# Board1_V4.net
KiCad netlist of a schematic drawn in EAGLE
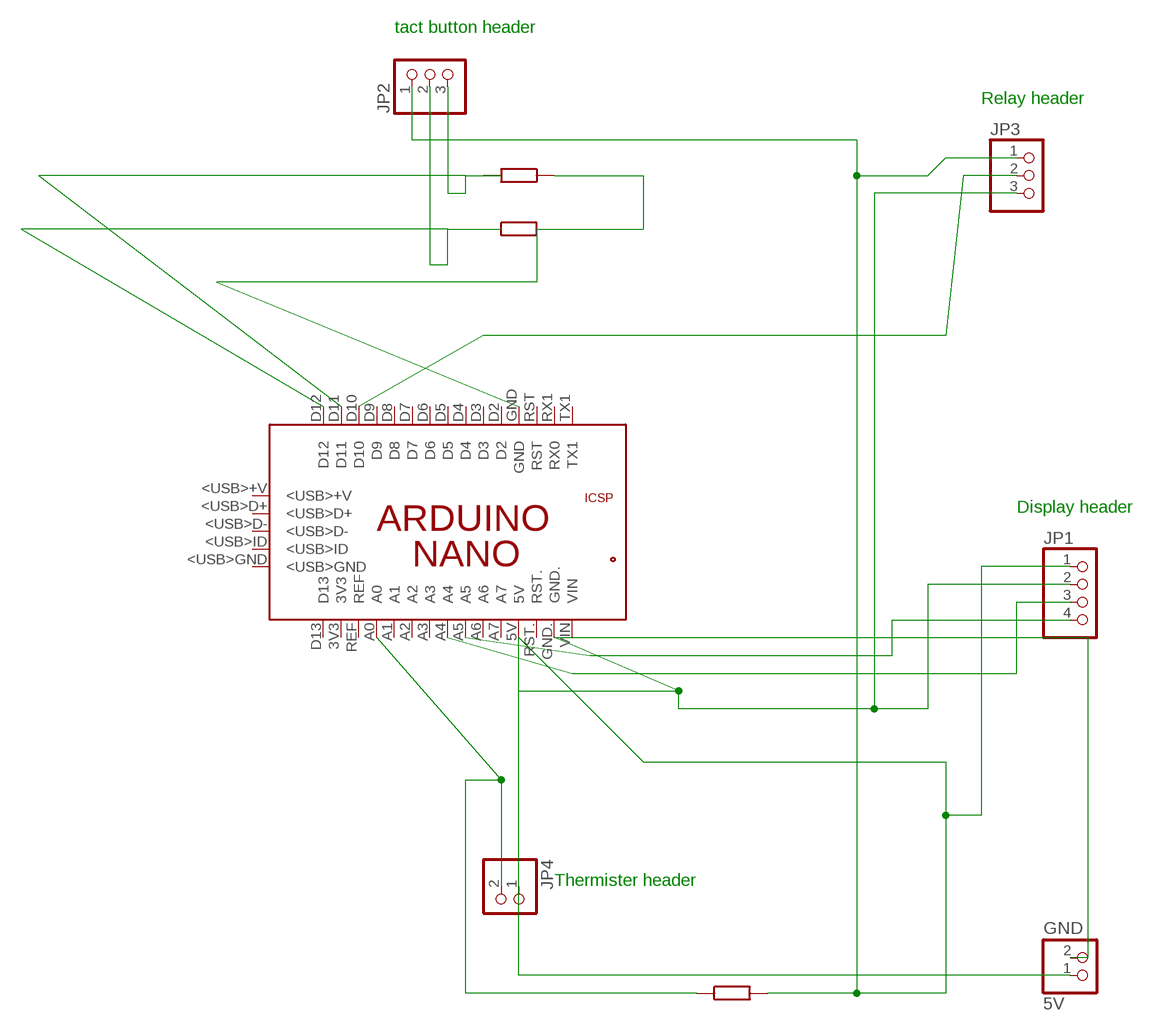
[diagram p0: schematic, sheet 1]

(export (version "E")
  (design (tool "Eeschema 10.0.6"))
  (components
    (comp (ref "5V")
      (value "GND")
      (footprint "eagle-import:1X02_90")
      (libsource (lib "eagle-import") (part "PINHD-1X2/90"))
    )
    (comp (ref "JP1")
      (value "PINHD-1X4/90")
      (footprint "eagle-import:1X04_90")
      (libsource (lib "eagle-import") (part "PINHD-1X4/90"))
    )
    (comp (ref "JP2")
      (value "PINHD-1X3/90")
      (footprint "eagle-import:1X03_90")
      (libsource (lib "eagle-import") (part "PINHD-1X3/90"))
    )
    (comp (ref "JP3")
      (value "PINHD-1X3/90")
      (footprint "eagle-import:1X03_90")
      (libsource (lib "eagle-import") (part "PINHD-1X3/90"))
    )
    (comp (ref "JP4")
      (value "PINHD-1X2/90")
      (footprint "eagle-import:1X02_90")
      (libsource (lib "eagle-import") (part "PINHD-1X2/90"))
    )
    (comp (ref "PCB1")
      (value "ARDUINO_NANO")
      (footprint "eagle-import:ARDUINO_NANO")
      (libsource (lib "eagle-import") (part "ARDUINO_NANO"))
    )
  )
  (nets
    (net (code "1") (name "Net-(5V-Pad1)") (class "Default")
      (node (ref "5V") (pin "1") (pinfunction "1_1") (pintype "passive"))
      (node (ref "JP1") (pin "1") (pinfunction "1_1") (pintype "passive"))
      (node (ref "JP2") (pin "1") (pinfunction "1_1") (pintype "passive"))
      (node (ref "JP3") (pin "1") (pinfunction "1_1") (pintype "passive"))
      (node (ref "PCB1") (pin "5V") (pinfunction "5V_5V") (pintype "bidirectional"))
    )
    (net (code "2") (name "Net-(5V-Pad2)") (class "Default")
      (node (ref "5V") (pin "2") (pinfunction "2_2") (pintype "passive"))
      (node (ref "JP1") (pin "2") (pinfunction "2_2") (pintype "passive"))
      (node (ref "JP3") (pin "3") (pinfunction "3_3") (pintype "passive"))
      (node (ref "JP4") (pin "1") (pinfunction "1_1") (pintype "passive"))
      (node (ref "PCB1") (pin "GND.") (pinfunction "GND._GND.") (pintype "bidirectional"))
    )
    (net (code "3") (name "Net-(JP1-Pad3)") (class "Default")
      (node (ref "JP1") (pin "3") (pinfunction "3_3") (pintype "passive"))
      (node (ref "PCB1") (pin "A4") (pinfunction "A4_A4") (pintype "bidirectional"))
    )
    (net (code "4") (name "Net-(JP1-Pad4)") (class "Default")
      (node (ref "JP1") (pin "4") (pinfunction "4_4") (pintype "passive"))
      (node (ref "PCB1") (pin "A5") (pinfunction "A5_A5") (pintype "bidirectional"))
    )
    (net (code "5") (name "Net-(JP2-Pad2)") (class "Default")
      (node (ref "JP2") (pin "2") (pinfunction "2_2") (pintype "passive"))
      (node (ref "PCB1") (pin "D12") (pinfunction "D12_D12") (pintype "bidirectional"))
    )
    (net (code "6") (name "Net-(JP2-Pad3)") (class "Default")
      (node (ref "JP2") (pin "3") (pinfunction "3_3") (pintype "passive"))
      (node (ref "PCB1") (pin "D11") (pinfunction "D11_D11") (pintype "bidirectional"))
    )
    (net (code "7") (name "Net-(JP3-Pad2)") (class "Default")
      (node (ref "JP3") (pin "2") (pinfunction "2_2") (pintype "passive"))
      (node (ref "PCB1") (pin "D10") (pinfunction "D10_D10") (pintype "bidirectional"))
    )
    (net (code "8") (name "Net-(JP4-Pad2)") (class "Default")
      (node (ref "JP4") (pin "2") (pinfunction "2_2") (pintype "passive"))
      (node (ref "PCB1") (pin "A0") (pinfunction "A0_A0") (pintype "bidirectional"))
    )
    (net (code "9") (name "unconnected-(PCB1-Pad3V3)") (class "Default")
      (node (ref "PCB1") (pin "3V3") (pinfunction "3V3_3V3") (pintype "bidirectional"))
    )
    (net (code "10") (name "unconnected-(PCB1-Pad5V.)") (class "Default")
      (node (ref "PCB1") (pin "5V.") (pinfunction "5V._5V.") (pintype "bidirectional"))
    )
    (net (code "11") (name "unconnected-(PCB1-Pad<USB>+V)") (class "Default")
      (node (ref "PCB1") (pin "<USB>+V") (pinfunction "<USB>+V_<USB>+V") (pintype "bidirectional"))
    )
    (net (code "12") (name "unconnected-(PCB1-Pad<USB>D+)") (class "Default")
      (node (ref "PCB1") (pin "<USB>D+") (pinfunction "<USB>D+_<USB>D+") (pintype "bidirectional"))
    )
    (net (code "13") (name "unconnected-(PCB1-Pad<USB>D-)") (class "Default")
      (node (ref "PCB1") (pin "<USB>D-") (pinfunction "<USB>D-_<USB>D-") (pintype "bidirectional"))
    )
    (net (code "14") (name "unconnected-(PCB1-Pad<USB>GND)") (class "Default")
      (node (ref "PCB1") (pin "<USB>GND") (pinfunction "<USB>GND_<USB>GND") (pintype "bidirectional"))
    )
    (net (code "15") (name "unconnected-(PCB1-Pad<USB>ID)") (class "Default")
      (node (ref "PCB1") (pin "<USB>ID") (pinfunction "<USB>ID_<USB>ID") (pintype "bidirectional"))
    )
    (net (code "16") (name "unconnected-(PCB1-PadA1)") (class "Default")
      (node (ref "PCB1") (pin "A1") (pinfunction "A1_A1") (pintype "bidirectional"))
    )
    (net (code "17") (name "unconnected-(PCB1-PadA2)") (class "Default")
      (node (ref "PCB1") (pin "A2") (pinfunction "A2_A2") (pintype "bidirectional"))
    )
    (net (code "18") (name "unconnected-(PCB1-PadA3)") (class "Default")
      (node (ref "PCB1") (pin "A3") (pinfunction "A3_A3") (pintype "bidirectional"))
    )
    (net (code "19") (name "unconnected-(PCB1-PadA6)") (class "Default")
      (node (ref "PCB1") (pin "A6") (pinfunction "A6_A6") (pintype "bidirectional"))
    )
    (net (code "20") (name "unconnected-(PCB1-PadA7)") (class "Default")
      (node (ref "PCB1") (pin "A7") (pinfunction "A7_A7") (pintype "bidirectional"))
    )
    (net (code "21") (name "unconnected-(PCB1-PadD2)") (class "Default")
      (node (ref "PCB1") (pin "D2") (pinfunction "D2_D2") (pintype "bidirectional"))
    )
    (net (code "22") (name "unconnected-(PCB1-PadD3)") (class "Default")
      (node (ref "PCB1") (pin "D3") (pinfunction "D3_D3") (pintype "bidirectional"))
    )
    (net (code "23") (name "unconnected-(PCB1-PadD4)") (class "Default")
      (node (ref "PCB1") (pin "D4") (pinfunction "D4_D4") (pintype "bidirectional"))
    )
    (net (code "24") (name "unconnected-(PCB1-PadD5)") (class "Default")
      (node (ref "PCB1") (pin "D5") (pinfunction "D5_D5") (pintype "bidirectional"))
    )
    (net (code "25") (name "unconnected-(PCB1-PadD6)") (class "Default")
      (node (ref "PCB1") (pin "D6") (pinfunction "D6_D6") (pintype "bidirectional"))
    )
    (net (code "26") (name "unconnected-(PCB1-PadD7)") (class "Default")
      (node (ref "PCB1") (pin "D7") (pinfunction "D7_D7") (pintype "bidirectional"))
    )
    (net (code "27") (name "unconnected-(PCB1-PadD8)") (class "Default")
      (node (ref "PCB1") (pin "D8") (pinfunction "D8_D8") (pintype "bidirectional"))
    )
    (net (code "28") (name "unconnected-(PCB1-PadD9)") (class "Default")
      (node (ref "PCB1") (pin "D9") (pinfunction "D9_D9") (pintype "bidirectional"))
    )
    (net (code "29") (name "unconnected-(PCB1-PadD13)") (class "Default")
      (node (ref "PCB1") (pin "D13") (pinfunction "D13_D13") (pintype "bidirectional"))
    )
    (net (code "30") (name "unconnected-(PCB1-PadGND)") (class "Default")
      (node (ref "PCB1") (pin "GND") (pinfunction "GND_GND") (pintype "bidirectional"))
    )
    (net (code "31") (name "unconnected-(PCB1-PadGND_)") (class "Default")
      (node (ref "PCB1") (pin "GND_") (pinfunction "GND__GND_") (pintype "bidirectional"))
    )
    (net (code "32") (name "unconnected-(PCB1-PadMISO)") (class "Default")
      (node (ref "PCB1") (pin "MISO") (pinfunction "MISO_MISO") (pintype "bidirectional"))
    )
    (net (code "33") (name "unconnected-(PCB1-PadMOSI)") (class "Default")
      (node (ref "PCB1") (pin "MOSI") (pinfunction "MOSI_MOSI") (pintype "bidirectional"))
    )
    (net (code "34") (name "unconnected-(PCB1-PadREF)") (class "Default")
      (node (ref "PCB1") (pin "REF") (pinfunction "REF_REF") (pintype "bidirectional"))
    )
    (net (code "35") (name "unconnected-(PCB1-PadRESET..)") (class "Default")
      (node (ref "PCB1") (pin "RESET..") (pinfunction "RESET.._RESET..") (pintype "bidirectional"))
    )
    (net (code "36") (name "unconnected-(PCB1-PadRST)") (class "Default")
      (node (ref "PCB1") (pin "RST") (pinfunction "RST_RST") (pintype "bidirectional"))
    )
    (net (code "37") (name "unconnected-(PCB1-PadRST.)") (class "Default")
      (node (ref "PCB1") (pin "RST.") (pinfunction "RST._RST.") (pintype "bidirectional"))
    )
    (net (code "38") (name "unconnected-(PCB1-PadSCK)") (class "Default")
      (node (ref "PCB1") (pin "SCK") (pinfunction "SCK_SCK") (pintype "bidirectional"))
    )
    (net (code "39") (name "unconnected-(PCB1-PadTX1)") (class "Default")
      (node (ref "PCB1") (pin "TX1") (pinfunction "TX1_TX1") (pintype "bidirectional"))
    )
    (net (code "40") (name "unconnected-(PCB1-PadVIN)") (class "Default")
      (node (ref "PCB1") (pin "VIN") (pinfunction "VIN_VIN") (pintype "bidirectional"))
    )
    (net (code "41") (name "unconnected-(PCB1-RX0-PadRX1)") (class "Default")
      (node (ref "PCB1") (pin "RX1") (pinfunction "RX0_RX1") (pintype "bidirectional"))
    )
  )
)
